# 1-WireThermocouple.net
KiCad netlist of a schematic drawn in EAGLE
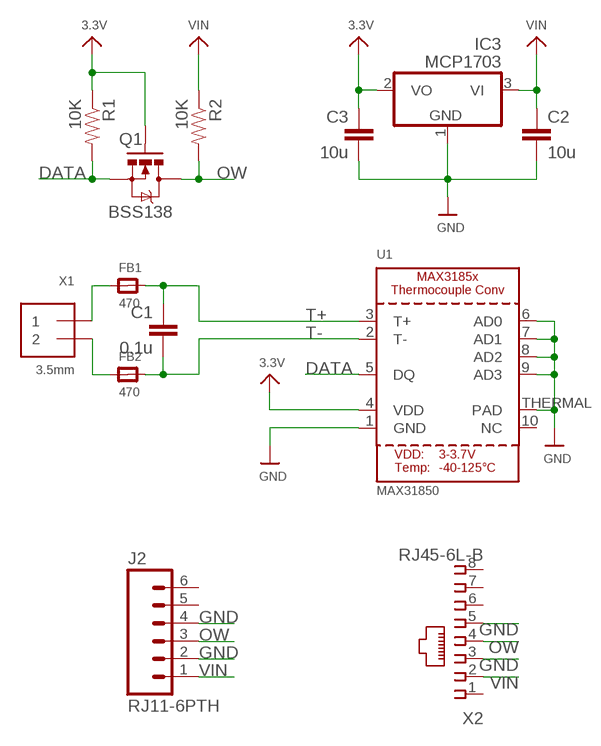
[diagram p0: schematic, sheet 1]

(export (version "E")
  (design (tool "Eeschema 10.0.6"))
  (components
    (comp (ref "C1")
      (value "0.1u")
      (footprint "eagle-import:0603-CAP")
      (libsource (lib "eagle-import") (part "CAP0603-CAP"))
    )
    (comp (ref "C2")
      (value "10u")
      (footprint "eagle-import:0603-CAP")
      (libsource (lib "eagle-import") (part "CAP0603-CAP"))
    )
    (comp (ref "C3")
      (value "10u")
      (footprint "eagle-import:0603-CAP")
      (libsource (lib "eagle-import") (part "CAP0603-CAP"))
    )
    (comp (ref "FB1")
      (value "470")
      (footprint "eagle-import:0603")
      (libsource (lib "eagle-import") (part "FERRITE"))
    )
    (comp (ref "FB2")
      (value "470")
      (footprint "eagle-import:0603")
      (libsource (lib "eagle-import") (part "FERRITE"))
    )
    (comp (ref "IC3")
      (value "MCP1703")
      (footprint "eagle-import:SOT23")
      (libsource (lib "eagle-import") (part "MCP1703CB"))
    )
    (comp (ref "J2")
      (value "RJ11-6PTH")
      (footprint "eagle-import:RJ11-6")
      (libsource (lib "eagle-import") (part "RJ11-6PTH"))
    )
    (comp (ref "Q1")
      (value "BSS138")
      (footprint "eagle-import:SOT23-3")
      (libsource (lib "eagle-import") (part "MOSFET-NCHANNELSMD"))
    )
    (comp (ref "R1")
      (value "10K")
      (footprint "eagle-import:0603-RES")
      (libsource (lib "eagle-import") (part "RESISTOR0603-RES"))
    )
    (comp (ref "R2")
      (value "10K")
      (footprint "eagle-import:0603-RES")
      (libsource (lib "eagle-import") (part "RESISTOR0603-RES"))
    )
    (comp (ref "U1")
      (value "MAX31850")
      (footprint "eagle-import:TDFN10_3X4MM")
      (libsource (lib "eagle-import") (part "MAX3185X"))
    )
    (comp (ref "X1")
      (value "3.5mm")
      (footprint "eagle-import:TERMBLOCK_1X2-3.5MM")
      (libsource (lib "eagle-import") (part "TERMBLOCK_1X2"))
    )
    (comp (ref "X2")
      (value "RJ45-6L-B")
      (footprint "eagle-import:RJ45-NO-SHIELD")
      (libsource (lib "eagle-import") (part "RJ45-6L-B"))
    )
  )
  (nets
    (net (code "1") (name "/DATA") (class "Default")
      (node (ref "Q1") (pin "2") (pinfunction "S_2") (pintype "passive"))
      (node (ref "R1") (pin "2") (pinfunction "2_2") (pintype "passive"))
      (node (ref "U1") (pin "5") (pinfunction "DQ_5") (pintype "bidirectional"))
    )
    (net (code "2") (name "/OW") (class "Default")
      (node (ref "J2") (pin "3") (pinfunction "3_3") (pintype "passive"))
      (node (ref "Q1") (pin "3") (pinfunction "D_3") (pintype "passive"))
      (node (ref "R2") (pin "2") (pinfunction "2_2") (pintype "passive"))
      (node (ref "X2") (pin "4") (pinfunction "4_4") (pintype "passive"))
    )
    (net (code "3") (name "/T+") (class "Default")
      (node (ref "C1") (pin "1") (pinfunction "1_1") (pintype "passive"))
      (node (ref "FB1") (pin "2") (pinfunction "P$2_2") (pintype "passive"))
      (node (ref "U1") (pin "3") (pinfunction "T+_3") (pintype "input"))
    )
    (net (code "4") (name "/T-") (class "Default")
      (node (ref "C1") (pin "2") (pinfunction "2_2") (pintype "passive"))
      (node (ref "FB2") (pin "2") (pinfunction "P$2_2") (pintype "passive"))
      (node (ref "U1") (pin "2") (pinfunction "T-_2") (pintype "input"))
    )
    (net (code "5") (name "3.3V") (class "Default")
      (node (ref "C3") (pin "1") (pinfunction "1_1") (pintype "passive"))
      (node (ref "IC3") (pin "2") (pinfunction "VO_2") (pintype "passive"))
      (node (ref "Q1") (pin "1") (pinfunction "G_1") (pintype "passive"))
      (node (ref "R1") (pin "1") (pinfunction "1_1") (pintype "passive"))
      (node (ref "U1") (pin "4") (pinfunction "VDD_4") (pintype "power_in"))
    )
    (net (code "6") (name "GND") (class "Default")
      (node (ref "C2") (pin "2") (pinfunction "2_2") (pintype "passive"))
      (node (ref "C3") (pin "2") (pinfunction "2_2") (pintype "passive"))
      (node (ref "IC3") (pin "1") (pinfunction "GND_1") (pintype "passive"))
      (node (ref "J2") (pin "2") (pinfunction "2_2") (pintype "passive"))
      (node (ref "J2") (pin "4") (pinfunction "4_4") (pintype "passive"))
      (node (ref "U1") (pin "1") (pinfunction "GND_1") (pintype "power_in"))
      (node (ref "U1") (pin "6") (pinfunction "AD0_6") (pintype "input"))
      (node (ref "U1") (pin "7") (pinfunction "AD1_7") (pintype "input"))
      (node (ref "U1") (pin "8") (pinfunction "AD2_8") (pintype "input"))
      (node (ref "U1") (pin "9") (pinfunction "AD3_9") (pintype "input"))
      (node (ref "U1") (pin "THERMAL") (pinfunction "PAD_THERMAL") (pintype "passive"))
      (node (ref "X2") (pin "3") (pinfunction "3_3") (pintype "passive"))
      (node (ref "X2") (pin "5") (pinfunction "5_5") (pintype "passive"))
    )
    (net (code "7") (name "Net-(FB1-P$1)") (class "Default")
      (node (ref "FB1") (pin "1") (pinfunction "P$1_1") (pintype "passive"))
      (node (ref "X1") (pin "1") (pinfunction "1_1") (pintype "passive"))
    )
    (net (code "8") (name "Net-(FB2-P$1)") (class "Default")
      (node (ref "FB2") (pin "1") (pinfunction "P$1_1") (pintype "passive"))
      (node (ref "X1") (pin "2") (pinfunction "2_2") (pintype "passive"))
    )
    (net (code "9") (name "VIN") (class "Default")
      (node (ref "C2") (pin "1") (pinfunction "1_1") (pintype "passive"))
      (node (ref "IC3") (pin "3") (pinfunction "VI_3") (pintype "input"))
      (node (ref "J2") (pin "1") (pinfunction "1_1") (pintype "passive"))
      (node (ref "R2") (pin "1") (pinfunction "1_1") (pintype "passive"))
      (node (ref "X2") (pin "2") (pinfunction "2_2") (pintype "passive"))
    )
    (net (code "10") (name "unconnected-(J2-Pad5)") (class "Default")
      (node (ref "J2") (pin "5") (pinfunction "5_5") (pintype "passive"))
    )
    (net (code "11") (name "unconnected-(J2-Pad6)") (class "Default")
      (node (ref "J2") (pin "6") (pinfunction "6_6") (pintype "passive"))
    )
    (net (code "12") (name "unconnected-(U1-NC-Pad10)") (class "Default")
      (node (ref "U1") (pin "10") (pinfunction "NC_10") (pintype "no_connect"))
    )
    (net (code "13") (name "unconnected-(X2-Pad1)") (class "Default")
      (node (ref "X2") (pin "1") (pinfunction "1_1") (pintype "passive"))
    )
    (net (code "14") (name "unconnected-(X2-Pad6)") (class "Default")
      (node (ref "X2") (pin "6") (pinfunction "6_6") (pintype "passive"))
    )
    (net (code "15") (name "unconnected-(X2-Pad7)") (class "Default")
      (node (ref "X2") (pin "7") (pinfunction "7_7") (pintype "passive"))
    )
    (net (code "16") (name "unconnected-(X2-Pad8)") (class "Default")
      (node (ref "X2") (pin "8") (pinfunction "8_8") (pintype "passive"))
    )
  )
)
